# MCU.net
KiCad netlist of a schematic drawn in Altium Designer
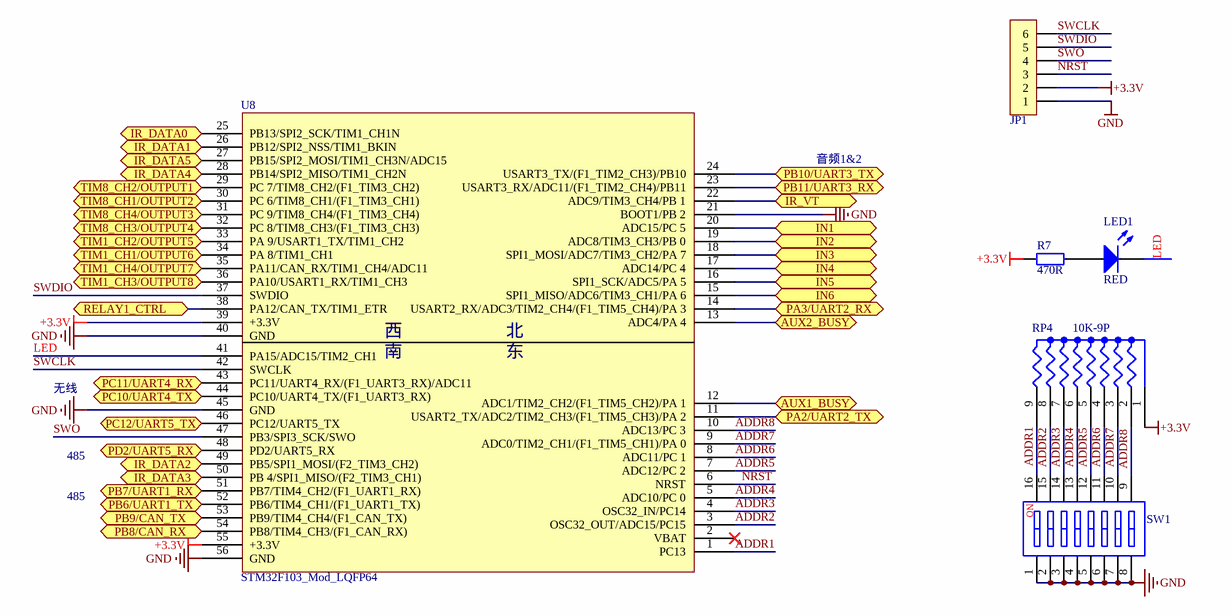
[diagram p0: MCU.SchDoc]

(export (version "E")
  (design (tool "Eeschema 10.0.6"))
  (components
    (comp (ref "JP1")
      (value "HDR-1X6")
      (footprint "XH2.54-6P")
      (description "6P接插件")
      (fields (field (name "版权归属") "源创客"))
      (libsource (lib "接插件") (part "Header 6"))
    )
    (comp (ref "LED1") (value "RED") (footprint "LED 5MM-R") (libsource (lib "any") (part "LED")))
    (comp (ref "R7") (value "470R") (footprint "R 0805") (libsource (lib "any") (part "Res1")))
    (comp (ref "RP4") (value "10K-9P") (libsource (lib "*") (part "RESNW_8/SIP9")))
    (comp (ref "SW1")
      (value "CSW-8P")
      (footprint "CSW DIP-8P_G")
      (description "8路编码开关")
      (fields (field (name "版权归属") "源创客"))
      (libsource (lib "按键-开关") (part "CSW-8P"))
    )
    (comp (ref "U8")
      (value "STM32F103_Mod_LQFP64")
      (footprint "STM32F103_LQFP64")
      (description "STM32F103RCT6")
      (libsource (lib "模块") (part "STM32F103_Mod_LQFP64"))
    )
  )
  (nets
    (net (code "1") (name "+3.3V") (class "Default")
      (node (ref "JP1") (pin "2") (pinfunction "2_2") (pintype "passive"))
      (node (ref "R7") (pin "2") (pinfunction "2_2") (pintype "passive"))
      (node (ref "RP4") (pin "1") (pinfunction "1_1") (pintype "passive"))
      (node (ref "U8") (pin "39") (pinfunction "+3.3V_39") (pintype "passive"))
      (node (ref "U8") (pin "55") (pinfunction "+3.3V_55") (pintype "passive"))
    )
    (net (code "2") (name "/ADDR1") (class "Default")
      (node (ref "RP4") (pin "9") (pinfunction "9_9") (pintype "passive"))
      (node (ref "SW1") (pin "16") (pinfunction "16_16") (pintype "passive"))
      (node (ref "U8") (pin "1") (pinfunction "PC13_1") (pintype "passive"))
    )
    (net (code "3") (name "/ADDR2") (class "Default")
      (node (ref "RP4") (pin "8") (pinfunction "8_8") (pintype "passive"))
      (node (ref "SW1") (pin "15") (pinfunction "15_15") (pintype "passive"))
      (node (ref "U8") (pin "3") (pinfunction "OSC32_OUT/ADC15/PC15_3") (pintype "passive"))
    )
    (net (code "4") (name "/ADDR3") (class "Default")
      (node (ref "RP4") (pin "7") (pinfunction "7_7") (pintype "passive"))
      (node (ref "SW1") (pin "14") (pinfunction "14_14") (pintype "passive"))
      (node (ref "U8") (pin "4") (pinfunction "OSC32_IN/PC14_4") (pintype "passive"))
    )
    (net (code "5") (name "/ADDR4") (class "Default")
      (node (ref "RP4") (pin "6") (pinfunction "6_6") (pintype "passive"))
      (node (ref "SW1") (pin "13") (pinfunction "13_13") (pintype "passive"))
      (node (ref "U8") (pin "5") (pinfunction "ADC10/PC_0_5") (pintype "passive"))
    )
    (net (code "6") (name "/ADDR5") (class "Default")
      (node (ref "RP4") (pin "5") (pinfunction "5_5") (pintype "passive"))
      (node (ref "SW1") (pin "12") (pinfunction "12_12") (pintype "passive"))
      (node (ref "U8") (pin "7") (pinfunction "ADC12/PC_2_7") (pintype "passive"))
    )
    (net (code "7") (name "/ADDR6") (class "Default")
      (node (ref "RP4") (pin "4") (pinfunction "4_4") (pintype "passive"))
      (node (ref "SW1") (pin "11") (pinfunction "11_11") (pintype "passive"))
      (node (ref "U8") (pin "8") (pinfunction "ADC11/PC_1_8") (pintype "passive"))
    )
    (net (code "8") (name "/ADDR7") (class "Default")
      (node (ref "RP4") (pin "3") (pinfunction "3_3") (pintype "passive"))
      (node (ref "SW1") (pin "10") (pinfunction "10_10") (pintype "passive"))
      (node (ref "U8") (pin "9") (pinfunction "ADC0/TIM2_CH1/(F1_TIM5_CH1)/PA_0_9") (pintype "passive"))
    )
    (net (code "9") (name "/ADDR8") (class "Default")
      (node (ref "RP4") (pin "2") (pinfunction "2_2") (pintype "passive"))
      (node (ref "SW1") (pin "9") (pinfunction "9_9") (pintype "passive"))
      (node (ref "U8") (pin "10") (pinfunction "ADC13/PC_3_10") (pintype "passive"))
    )
    (net (code "10") (name "/AUX1_BUSY") (class "Default")
      (node (ref "U8") (pin "12") (pinfunction "ADC1/TIM2_CH2/(F1_TIM5_CH2)/PA_1_12") (pintype "passive"))
    )
    (net (code "11") (name "/AUX2_BUSY") (class "Default")
      (node (ref "U8") (pin "13") (pinfunction "ADC4/PA_4_13") (pintype "passive"))
    )
    (net (code "12") (name "/IN1") (class "Default")
      (node (ref "U8") (pin "20") (pinfunction "ADC15/PC_5_20") (pintype "passive"))
    )
    (net (code "13") (name "/IN2") (class "Default")
      (node (ref "U8") (pin "19") (pinfunction "ADC8/TIM3_CH3/PB_0_19") (pintype "passive"))
    )
    (net (code "14") (name "/IN3") (class "Default")
      (node (ref "U8") (pin "18") (pinfunction "SPI1_MOSI/ADC7/TIM3_CH2/PA_7_18") (pintype "passive"))
    )
    (net (code "15") (name "/IN4") (class "Default")
      (node (ref "U8") (pin "17") (pinfunction "ADC14/PC_4_17") (pintype "passive"))
    )
    (net (code "16") (name "/IN5") (class "Default")
      (node (ref "U8") (pin "16") (pinfunction "SPI1_SCK/ADC5/PA_5_16") (pintype "passive"))
    )
    (net (code "17") (name "/IN6") (class "Default")
      (node (ref "U8") (pin "15") (pinfunction "SPI1_MISO/ADC6/TIM3_CH1/PA_6_15") (pintype "passive"))
    )
    (net (code "18") (name "/IR_DATA0") (class "Default")
      (node (ref "U8") (pin "25") (pinfunction "PB13/SPI2_SCK/TIM1_CH1N_25") (pintype "passive"))
    )
    (net (code "19") (name "/IR_DATA1") (class "Default")
      (node (ref "U8") (pin "26") (pinfunction "PB12/SPI2_NSS/TIM1_BKIN_26") (pintype "passive"))
    )
    (net (code "20") (name "/IR_DATA2") (class "Default")
      (node (ref "U8") (pin "49") (pinfunction "PB5/SPI1_MOSI/(F2_TIM3_CH2)_49") (pintype "passive"))
    )
    (net (code "21") (name "/IR_DATA3") (class "Default")
      (node (ref "U8") (pin "50") (pinfunction "PB_4/SPI1_MISO/(F2_TIM3_CH1)_50") (pintype "passive"))
    )
    (net (code "22") (name "/IR_DATA4") (class "Default")
      (node (ref "U8") (pin "28") (pinfunction "PB14/SPI2_MISO/TIM1_CH2N_28") (pintype "passive"))
    )
    (net (code "23") (name "/IR_DATA5") (class "Default")
      (node (ref "U8") (pin "27") (pinfunction "PB15/SPI2_MOSI/TIM1_CH3N/ADC15_27") (pintype "passive"))
    )
    (net (code "24") (name "/IR_VT") (class "Default")
      (node (ref "U8") (pin "22") (pinfunction "ADC9/TIM3_CH4/PB_1_22") (pintype "passive"))
    )
    (net (code "25") (name "/LED") (class "Default")
      (node (ref "LED1") (pin "2") (pinfunction "K_2") (pintype "passive"))
      (node (ref "U8") (pin "41") (pinfunction "PA15/ADC15/TIM2_CH1_41") (pintype "passive"))
    )
    (net (code "26") (name "/NRST") (class "Default")
      (node (ref "JP1") (pin "3") (pinfunction "3_3") (pintype "passive"))
      (node (ref "U8") (pin "6") (pinfunction "NRST_6") (pintype "passive"))
    )
    (net (code "27") (name "/PA2{slash}UART2_TX") (class "Default")
      (node (ref "U8") (pin "11") (pinfunction "USART2_TX/ADC2/TIM2_CH3/(F1_TIM5_CH3)/PA_2_11") (pintype "passive"))
    )
    (net (code "28") (name "/PA3{slash}UART2_RX") (class "Default")
      (node (ref "U8") (pin "14") (pinfunction "USART2_RX/ADC3/TIM2_CH4/(F1_TIM5_CH4)/PA_3_14") (pintype "passive"))
    )
    (net (code "29") (name "/PB6{slash}UART1_TX") (class "Default")
      (node (ref "U8") (pin "52") (pinfunction "PB6/TIM4_CH1/(F1_UART1_TX)_52") (pintype "passive"))
    )
    (net (code "30") (name "/PB7{slash}UART1_RX") (class "Default")
      (node (ref "U8") (pin "51") (pinfunction "PB7/TIM4_CH2/(F1_UART1_RX)_51") (pintype "passive"))
    )
    (net (code "31") (name "/PB8{slash}CAN_RX") (class "Default")
      (node (ref "U8") (pin "54") (pinfunction "PB8/TIM4_CH3/(F1_CAN_RX)_54") (pintype "passive"))
    )
    (net (code "32") (name "/PB9{slash}CAN_TX") (class "Default")
      (node (ref "U8") (pin "53") (pinfunction "PB9/TIM4_CH4/(F1_CAN_TX)_53") (pintype "passive"))
    )
    (net (code "33") (name "/PB10{slash}UART3_TX") (class "Default")
      (node (ref "U8") (pin "24") (pinfunction "USART3_TX/(F1_TIM2_CH3)/PB10_24") (pintype "passive"))
    )
    (net (code "34") (name "/PB11{slash}UART3_RX") (class "Default")
      (node (ref "U8") (pin "23") (pinfunction "USART3_RX/ADC11/(F1_TIM2_CH4)/PB11_23") (pintype "passive"))
    )
    (net (code "35") (name "/PC10{slash}UART4_TX") (class "Default")
      (node (ref "U8") (pin "44") (pinfunction "PC10/UART4_TX/(F1_UART3_RX)_44") (pintype "passive"))
    )
    (net (code "36") (name "/PC11{slash}UART4_RX") (class "Default")
      (node (ref "U8") (pin "43") (pinfunction "PC11/UART4_RX/(F1_UART3_RX)/ADC11_43") (pintype "passive"))
    )
    (net (code "37") (name "/PC12{slash}UART5_TX") (class "Default")
      (node (ref "U8") (pin "46") (pinfunction "PC12/UART5_TX_46") (pintype "passive"))
    )
    (net (code "38") (name "/PD2{slash}UART5_RX") (class "Default")
      (node (ref "U8") (pin "48") (pinfunction "PD2/UART5_RX_48") (pintype "passive"))
    )
    (net (code "39") (name "/RELAY1_CTRL") (class "Default")
      (node (ref "U8") (pin "38") (pinfunction "PA12/CAN_TX/TIM1_ETR_38") (pintype "passive"))
    )
    (net (code "40") (name "/SWCLK") (class "Default")
      (node (ref "JP1") (pin "6") (pinfunction "6_6") (pintype "passive"))
      (node (ref "U8") (pin "42") (pinfunction "SWCLK_42") (pintype "passive"))
    )
    (net (code "41") (name "/SWDIO") (class "Default")
      (node (ref "JP1") (pin "5") (pinfunction "5_5") (pintype "passive"))
      (node (ref "U8") (pin "37") (pinfunction "SWDIO_37") (pintype "passive"))
    )
    (net (code "42") (name "/SWO") (class "Default")
      (node (ref "JP1") (pin "4") (pinfunction "4_4") (pintype "passive"))
      (node (ref "U8") (pin "47") (pinfunction "PB3/SPI3_SCK/SWO_47") (pintype "passive"))
    )
    (net (code "43") (name "/TIM1_CH1{slash}OUTPUT6") (class "Default")
      (node (ref "U8") (pin "34") (pinfunction "PA_8/TIM1_CH1_34") (pintype "passive"))
    )
    (net (code "44") (name "/TIM1_CH2{slash}OUTPUT5") (class "Default")
      (node (ref "U8") (pin "33") (pinfunction "PA_9/USART1_TX/TIM1_CH2_33") (pintype "passive"))
    )
    (net (code "45") (name "/TIM1_CH3{slash}OUTPUT8") (class "Default")
      (node (ref "U8") (pin "36") (pinfunction "PA10/USART1_RX/TIM1_CH3_36") (pintype "passive"))
    )
    (net (code "46") (name "/TIM1_CH4{slash}OUTPUT7") (class "Default")
      (node (ref "U8") (pin "35") (pinfunction "PA11/CAN_RX/TIM1_CH4/ADC11_35") (pintype "passive"))
    )
    (net (code "47") (name "/TIM8_CH1{slash}OUTPUT2") (class "Default")
      (node (ref "U8") (pin "30") (pinfunction "PC_6/TIM8_CH1/(F1_TIM3_CH1)_30") (pintype "passive"))
    )
    (net (code "48") (name "/TIM8_CH2{slash}OUTPUT1") (class "Default")
      (node (ref "U8") (pin "29") (pinfunction "PC_7/TIM8_CH2/(F1_TIM3_CH2)_29") (pintype "passive"))
    )
    (net (code "49") (name "/TIM8_CH3{slash}OUTPUT4") (class "Default")
      (node (ref "U8") (pin "32") (pinfunction "PC_8/TIM8_CH3/(F1_TIM3_CH3)_32") (pintype "passive"))
    )
    (net (code "50") (name "/TIM8_CH4{slash}OUTPUT3") (class "Default")
      (node (ref "U8") (pin "31") (pinfunction "PC_9/TIM8_CH4/(F1_TIM3_CH4)_31") (pintype "passive"))
    )
    (net (code "51") (name "GND") (class "Default")
      (node (ref "JP1") (pin "1") (pinfunction "1_1") (pintype "passive"))
      (node (ref "SW1") (pin "1") (pinfunction "1_1") (pintype "passive"))
      (node (ref "SW1") (pin "2") (pinfunction "2_2") (pintype "passive"))
      (node (ref "SW1") (pin "3") (pinfunction "3_3") (pintype "passive"))
      (node (ref "SW1") (pin "4") (pinfunction "4_4") (pintype "passive"))
      (node (ref "SW1") (pin "5") (pinfunction "5_5") (pintype "passive"))
      (node (ref "SW1") (pin "6") (pinfunction "6_6") (pintype "passive"))
      (node (ref "SW1") (pin "7") (pinfunction "7_7") (pintype "passive"))
      (node (ref "SW1") (pin "8") (pinfunction "8_8") (pintype "passive"))
      (node (ref "U8") (pin "21") (pinfunction "BOOT1/PB_2_21") (pintype "passive"))
      (node (ref "U8") (pin "40") (pinfunction "GND_40") (pintype "passive"))
      (node (ref "U8") (pin "45") (pinfunction "GND_45") (pintype "passive"))
      (node (ref "U8") (pin "56") (pinfunction "GND_56") (pintype "passive"))
    )
    (net (code "52") (name "Net-(LED1-A)") (class "Default")
      (node (ref "LED1") (pin "1") (pinfunction "A_1") (pintype "passive"))
      (node (ref "R7") (pin "1") (pinfunction "1_1") (pintype "passive"))
    )
    (net (code "53") (name "unconnected-(U8-VBAT-Pad2)") (class "Default")
      (node (ref "U8") (pin "2") (pinfunction "VBAT_2") (pintype "passive+no_connect"))
    )
  )
)
